# nano.net
KiCad netlist of a schematic drawn in EAGLE
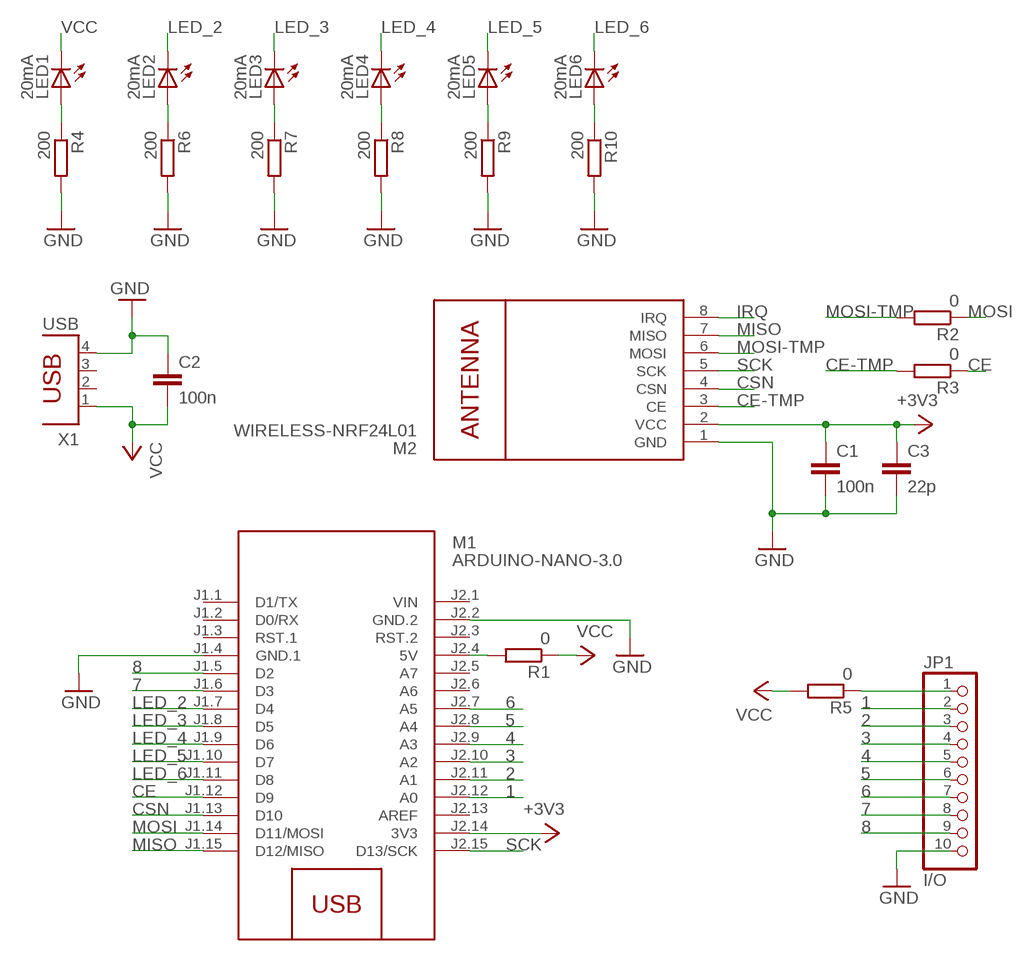
[diagram p0: schematic, sheet 1]

(export (version "E")
  (design (tool "Eeschema 10.0.6"))
  (components
    (comp (ref "C1")
      (value "100n")
      (footprint "eagle-import:C1206")
      (libsource (lib "eagle-import") (part "C-EUC1206"))
    )
    (comp (ref "C2")
      (value "100n")
      (footprint "eagle-import:C1206")
      (libsource (lib "eagle-import") (part "C-EUC1206"))
    )
    (comp (ref "C3")
      (value "22p")
      (footprint "eagle-import:C1206")
      (libsource (lib "eagle-import") (part "C-EUC1206"))
    )
    (comp (ref "JP1")
      (value "I/O")
      (footprint "eagle-import:1X10")
      (libsource (lib "eagle-import") (part "PINHD-1X10"))
    )
    (comp (ref "LED1")
      (value "20mA")
      (footprint "eagle-import:CHIPLED_1206")
      (libsource (lib "eagle-import") (part "LEDCHIPLED_1206"))
    )
    (comp (ref "LED2")
      (value "20mA")
      (footprint "eagle-import:CHIPLED_1206")
      (libsource (lib "eagle-import") (part "LEDCHIPLED_1206"))
    )
    (comp (ref "LED3")
      (value "20mA")
      (footprint "eagle-import:CHIPLED_1206")
      (libsource (lib "eagle-import") (part "LEDCHIPLED_1206"))
    )
    (comp (ref "LED4")
      (value "20mA")
      (footprint "eagle-import:CHIPLED_1206")
      (libsource (lib "eagle-import") (part "LEDCHIPLED_1206"))
    )
    (comp (ref "LED5")
      (value "20mA")
      (footprint "eagle-import:CHIPLED_1206")
      (libsource (lib "eagle-import") (part "LEDCHIPLED_1206"))
    )
    (comp (ref "LED6")
      (value "20mA")
      (footprint "eagle-import:CHIPLED_1206")
      (libsource (lib "eagle-import") (part "LEDCHIPLED_1206"))
    )
    (comp (ref "M1")
      (value "ARDUINO-NANO-3.0")
      (footprint "eagle-import:ARDUINO-NANO-3.0")
      (libsource (lib "eagle-import") (part "ARDUINO-NANO-3.0"))
    )
    (comp (ref "M2")
      (value "WIRELESS-NRF24L01")
      (footprint "eagle-import:WIRELESS-NRF24L01")
      (libsource (lib "eagle-import") (part "WIRELESS-NRF24L01"))
    )
    (comp (ref "R1")
      (value "0")
      (footprint "eagle-import:R1206")
      (libsource (lib "eagle-import") (part "R-EU_R1206"))
    )
    (comp (ref "R2")
      (value "0")
      (footprint "eagle-import:R1206")
      (libsource (lib "eagle-import") (part "R-EU_R1206"))
    )
    (comp (ref "R3")
      (value "0")
      (footprint "eagle-import:R1206")
      (libsource (lib "eagle-import") (part "R-EU_R1206"))
    )
    (comp (ref "R4")
      (value "200")
      (footprint "eagle-import:R1206")
      (libsource (lib "eagle-import") (part "R-EU_R1206"))
    )
    (comp (ref "R5")
      (value "0")
      (footprint "eagle-import:R1206")
      (libsource (lib "eagle-import") (part "R-EU_R1206"))
    )
    (comp (ref "R6")
      (value "200")
      (footprint "eagle-import:R1206")
      (libsource (lib "eagle-import") (part "R-EU_R1206"))
    )
    (comp (ref "R7")
      (value "200")
      (footprint "eagle-import:R1206")
      (libsource (lib "eagle-import") (part "R-EU_R1206"))
    )
    (comp (ref "R8")
      (value "200")
      (footprint "eagle-import:R1206")
      (libsource (lib "eagle-import") (part "R-EU_R1206"))
    )
    (comp (ref "R9")
      (value "200")
      (footprint "eagle-import:R1206")
      (libsource (lib "eagle-import") (part "R-EU_R1206"))
    )
    (comp (ref "R10")
      (value "200")
      (footprint "eagle-import:R1206")
      (libsource (lib "eagle-import") (part "R-EU_R1206"))
    )
    (comp (ref "X1")
      (value "USB")
      (footprint "eagle-import:PN87520")
      (libsource (lib "eagle-import") (part "PN87520"))
    )
  )
  (nets
    (net (code "1") (name "+3V3") (class "Default")
      (node (ref "C1") (pin "1") (pinfunction "1_1") (pintype "passive"))
      (node (ref "C3") (pin "1") (pinfunction "1_1") (pintype "passive"))
      (node (ref "M1") (pin "J2.14") (pinfunction "3V3_J2.14") (pintype "power_in"))
      (node (ref "M2") (pin "2") (pinfunction "VCC_2") (pintype "power_in"))
    )
    (net (code "2") (name "/1") (class "Default")
      (node (ref "JP1") (pin "2") (pinfunction "2_2") (pintype "passive"))
      (node (ref "M1") (pin "J2.12") (pinfunction "A0_J2.12") (pintype "bidirectional"))
    )
    (net (code "3") (name "/2") (class "Default")
      (node (ref "JP1") (pin "3") (pinfunction "3_3") (pintype "passive"))
      (node (ref "M1") (pin "J2.11") (pinfunction "A1_J2.11") (pintype "bidirectional"))
    )
    (net (code "4") (name "/3") (class "Default")
      (node (ref "JP1") (pin "4") (pinfunction "4_4") (pintype "passive"))
      (node (ref "M1") (pin "J2.10") (pinfunction "A2_J2.10") (pintype "bidirectional"))
    )
    (net (code "5") (name "/4") (class "Default")
      (node (ref "JP1") (pin "5") (pinfunction "5_5") (pintype "passive"))
      (node (ref "M1") (pin "J2.9") (pinfunction "A3_J2.9") (pintype "bidirectional"))
    )
    (net (code "6") (name "/5") (class "Default")
      (node (ref "JP1") (pin "6") (pinfunction "6_6") (pintype "passive"))
      (node (ref "M1") (pin "J2.8") (pinfunction "A4_J2.8") (pintype "bidirectional"))
    )
    (net (code "7") (name "/6") (class "Default")
      (node (ref "JP1") (pin "7") (pinfunction "7_7") (pintype "passive"))
      (node (ref "M1") (pin "J2.7") (pinfunction "A5_J2.7") (pintype "bidirectional"))
    )
    (net (code "8") (name "/7") (class "Default")
      (node (ref "JP1") (pin "8") (pinfunction "8_8") (pintype "passive"))
      (node (ref "M1") (pin "J1.6") (pinfunction "D3_J1.6") (pintype "bidirectional"))
    )
    (net (code "9") (name "/8") (class "Default")
      (node (ref "JP1") (pin "9") (pinfunction "9_9") (pintype "passive"))
      (node (ref "M1") (pin "J1.5") (pinfunction "D2_J1.5") (pintype "bidirectional"))
    )
    (net (code "10") (name "/CE") (class "Default")
      (node (ref "M1") (pin "J1.12") (pinfunction "D9_J1.12") (pintype "bidirectional"))
      (node (ref "R3") (pin "1") (pinfunction "1_1") (pintype "passive"))
    )
    (net (code "11") (name "/CE-TMP") (class "Default")
      (node (ref "M2") (pin "3") (pinfunction "CE_3") (pintype "bidirectional"))
      (node (ref "R3") (pin "2") (pinfunction "2_2") (pintype "passive"))
    )
    (net (code "12") (name "/CSN") (class "Default")
      (node (ref "M1") (pin "J1.13") (pinfunction "D10_J1.13") (pintype "bidirectional"))
      (node (ref "M2") (pin "4") (pinfunction "CSN_4") (pintype "bidirectional"))
    )
    (net (code "13") (name "/IRQ") (class "Default")
      (node (ref "M2") (pin "8") (pinfunction "IRQ_8") (pintype "bidirectional"))
    )
    (net (code "14") (name "/LED_2") (class "Default")
      (node (ref "LED2") (pin "C") (pinfunction "C_C") (pintype "passive"))
      (node (ref "M1") (pin "J1.7") (pinfunction "D4_J1.7") (pintype "bidirectional"))
    )
    (net (code "15") (name "/LED_3") (class "Default")
      (node (ref "LED3") (pin "C") (pinfunction "C_C") (pintype "passive"))
      (node (ref "M1") (pin "J1.8") (pinfunction "D5_J1.8") (pintype "bidirectional"))
    )
    (net (code "16") (name "/LED_4") (class "Default")
      (node (ref "LED4") (pin "C") (pinfunction "C_C") (pintype "passive"))
      (node (ref "M1") (pin "J1.9") (pinfunction "D6_J1.9") (pintype "bidirectional"))
    )
    (net (code "17") (name "/LED_5") (class "Default")
      (node (ref "LED5") (pin "C") (pinfunction "C_C") (pintype "passive"))
      (node (ref "M1") (pin "J1.10") (pinfunction "D7_J1.10") (pintype "bidirectional"))
    )
    (net (code "18") (name "/LED_6") (class "Default")
      (node (ref "LED6") (pin "C") (pinfunction "C_C") (pintype "passive"))
      (node (ref "M1") (pin "J1.11") (pinfunction "D8_J1.11") (pintype "bidirectional"))
    )
    (net (code "19") (name "/MISO") (class "Default")
      (node (ref "M1") (pin "J1.15") (pinfunction "D12/MISO_J1.15") (pintype "bidirectional"))
      (node (ref "M2") (pin "7") (pinfunction "MISO_7") (pintype "bidirectional"))
    )
    (net (code "20") (name "/MOSI") (class "Default")
      (node (ref "M1") (pin "J1.14") (pinfunction "D11/MOSI_J1.14") (pintype "bidirectional"))
      (node (ref "R2") (pin "1") (pinfunction "1_1") (pintype "passive"))
    )
    (net (code "21") (name "/MOSI-TMP") (class "Default")
      (node (ref "M2") (pin "6") (pinfunction "MOSI_6") (pintype "bidirectional"))
      (node (ref "R2") (pin "2") (pinfunction "2_2") (pintype "passive"))
    )
    (net (code "22") (name "/SCK") (class "Default")
      (node (ref "M1") (pin "J2.15") (pinfunction "D13/SCK_J2.15") (pintype "bidirectional"))
      (node (ref "M2") (pin "5") (pinfunction "SCK_5") (pintype "bidirectional"))
    )
    (net (code "23") (name "/VIN") (class "Default")
      (node (ref "M1") (pin "J2.1") (pinfunction "VIN_J2.1") (pintype "power_in"))
    )
    (net (code "24") (name "GND") (class "Default")
      (node (ref "C1") (pin "2") (pinfunction "2_2") (pintype "passive"))
      (node (ref "C2") (pin "1") (pinfunction "1_1") (pintype "passive"))
      (node (ref "C3") (pin "2") (pinfunction "2_2") (pintype "passive"))
      (node (ref "JP1") (pin "10") (pinfunction "10_10") (pintype "passive"))
      (node (ref "M1") (pin "J1.4") (pinfunction "GND.1_J1.4") (pintype "power_in"))
      (node (ref "M1") (pin "J2.2") (pinfunction "GND.2_J2.2") (pintype "power_in"))
      (node (ref "M2") (pin "1") (pinfunction "GND_1") (pintype "power_in"))
      (node (ref "R10") (pin "2") (pinfunction "2_2") (pintype "passive"))
      (node (ref "R4") (pin "2") (pinfunction "2_2") (pintype "passive"))
      (node (ref "R6") (pin "2") (pinfunction "2_2") (pintype "passive"))
      (node (ref "R7") (pin "2") (pinfunction "2_2") (pintype "passive"))
      (node (ref "R8") (pin "2") (pinfunction "2_2") (pintype "passive"))
      (node (ref "R9") (pin "2") (pinfunction "2_2") (pintype "passive"))
      (node (ref "X1") (pin "4") (pinfunction "4_4") (pintype "passive"))
    )
    (net (code "25") (name "Net-(JP1-Pad1)") (class "Default")
      (node (ref "JP1") (pin "1") (pinfunction "1_1") (pintype "passive"))
      (node (ref "R5") (pin "1") (pinfunction "1_1") (pintype "passive"))
    )
    (net (code "26") (name "Net-(LED1-PadA)") (class "Default")
      (node (ref "LED1") (pin "A") (pinfunction "A_A") (pintype "passive"))
      (node (ref "R4") (pin "1") (pinfunction "1_1") (pintype "passive"))
    )
    (net (code "27") (name "Net-(LED2-PadA)") (class "Default")
      (node (ref "LED2") (pin "A") (pinfunction "A_A") (pintype "passive"))
      (node (ref "R6") (pin "1") (pinfunction "1_1") (pintype "passive"))
    )
    (net (code "28") (name "Net-(LED3-PadA)") (class "Default")
      (node (ref "LED3") (pin "A") (pinfunction "A_A") (pintype "passive"))
      (node (ref "R7") (pin "1") (pinfunction "1_1") (pintype "passive"))
    )
    (net (code "29") (name "Net-(LED4-PadA)") (class "Default")
      (node (ref "LED4") (pin "A") (pinfunction "A_A") (pintype "passive"))
      (node (ref "R8") (pin "1") (pinfunction "1_1") (pintype "passive"))
    )
    (net (code "30") (name "Net-(LED5-PadA)") (class "Default")
      (node (ref "LED5") (pin "A") (pinfunction "A_A") (pintype "passive"))
      (node (ref "R9") (pin "1") (pinfunction "1_1") (pintype "passive"))
    )
    (net (code "31") (name "Net-(LED6-PadA)") (class "Default")
      (node (ref "LED6") (pin "A") (pinfunction "A_A") (pintype "passive"))
      (node (ref "R10") (pin "1") (pinfunction "1_1") (pintype "passive"))
    )
    (net (code "32") (name "Net-(M1-5V)") (class "Default")
      (node (ref "M1") (pin "J2.4") (pinfunction "5V_J2.4") (pintype "power_in"))
      (node (ref "R1") (pin "2") (pinfunction "2_2") (pintype "passive"))
    )
    (net (code "33") (name "VCC") (class "Default")
      (node (ref "C2") (pin "2") (pinfunction "2_2") (pintype "passive"))
      (node (ref "LED1") (pin "C") (pinfunction "C_C") (pintype "passive"))
      (node (ref "R1") (pin "1") (pinfunction "1_1") (pintype "passive"))
      (node (ref "R5") (pin "2") (pinfunction "2_2") (pintype "passive"))
      (node (ref "X1") (pin "1") (pinfunction "1_1") (pintype "passive"))
    )
    (net (code "34") (name "unconnected-(M1-A6-PadJ2.6)") (class "Default")
      (node (ref "M1") (pin "J2.6") (pinfunction "A6_J2.6") (pintype "bidirectional"))
    )
    (net (code "35") (name "unconnected-(M1-A7-PadJ2.5)") (class "Default")
      (node (ref "M1") (pin "J2.5") (pinfunction "A7_J2.5") (pintype "bidirectional"))
    )
    (net (code "36") (name "unconnected-(M1-AREF-PadJ2.13)") (class "Default")
      (node (ref "M1") (pin "J2.13") (pinfunction "AREF_J2.13") (pintype "bidirectional"))
    )
    (net (code "37") (name "unconnected-(M1-D0{slash}RX-PadJ1.2)") (class "Default")
      (node (ref "M1") (pin "J1.2") (pinfunction "D0/RX_J1.2") (pintype "bidirectional"))
    )
    (net (code "38") (name "unconnected-(M1-D1{slash}TX-PadJ1.1)") (class "Default")
      (node (ref "M1") (pin "J1.1") (pinfunction "D1/TX_J1.1") (pintype "bidirectional"))
    )
    (net (code "39") (name "unconnected-(M1-RST.1-PadJ1.3)") (class "Default")
      (node (ref "M1") (pin "J1.3") (pinfunction "RST.1_J1.3") (pintype "bidirectional"))
    )
    (net (code "40") (name "unconnected-(M1-RST.2-PadJ2.3)") (class "Default")
      (node (ref "M1") (pin "J2.3") (pinfunction "RST.2_J2.3") (pintype "bidirectional"))
    )
    (net (code "41") (name "unconnected-(X1-Pad2)") (class "Default")
      (node (ref "X1") (pin "2") (pinfunction "2_2") (pintype "passive"))
    )
    (net (code "42") (name "unconnected-(X1-Pad3)") (class "Default")
      (node (ref "X1") (pin "3") (pinfunction "3_3") (pintype "passive"))
    )
  )
)
